# Measurement_REO.net
KiCad netlist of a schematic drawn in Altium Designer
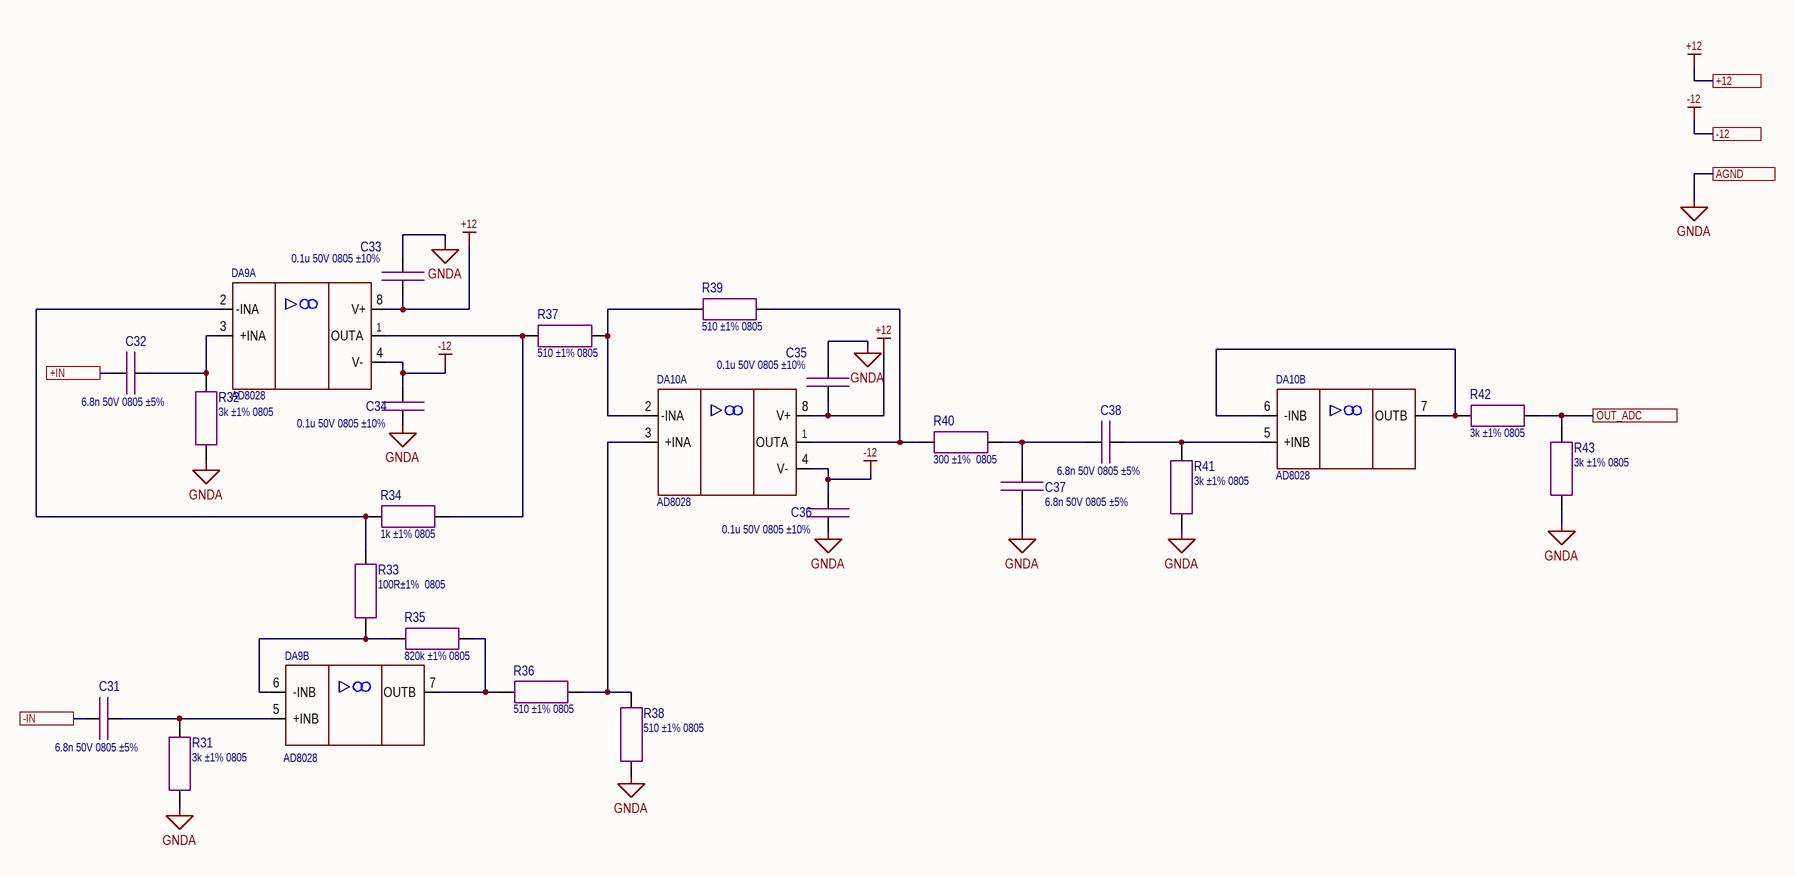
[diagram p0: Measurement_REO.SchDoc]

(export (version "E")
  (design (tool "Eeschema 10.0.6"))
  (components
    (comp (ref "C31")
      (value "6.8n 50V 0805 ±5%")
      (footprint "CAP: SMD 0805 MD IPC 782")
      (libsource (lib "UOMP_capacitors") (part "6.8n 50V 0805 ±5%"))
    )
    (comp (ref "C32")
      (value "6.8n 50V 0805 ±5%")
      (footprint "CAP: SMD 0805 MD IPC 782")
      (libsource (lib "UOMP_capacitors") (part "6.8n 50V 0805 ±5%"))
    )
    (comp (ref "C33")
      (value "0.1u 50V 0805 ±10%")
      (footprint "CAP: SMD 0805 MD IPC 782")
      (libsource (lib "UOMP capacitors") (part "0.1u 50V 0805 ±10%"))
    )
    (comp (ref "C34")
      (value "0.1u 50V 0805 ±10%")
      (footprint "CAP: SMD 0805 MD IPC 782")
      (libsource (lib "UOMP capacitors") (part "0.1u 50V 0805 ±10%"))
    )
    (comp (ref "C35")
      (value "0.1u 50V 0805 ±10%")
      (footprint "CAP: SMD 0805 MD IPC 782")
      (libsource (lib "UOMP capacitors") (part "0.1u 50V 0805 ±10%"))
    )
    (comp (ref "C36")
      (value "0.1u 50V 0805 ±10%")
      (footprint "CAP: SMD 0805 MD IPC 782")
      (libsource (lib "UOMP capacitors") (part "0.1u 50V 0805 ±10%"))
    )
    (comp (ref "C37")
      (value "6.8n 50V 0805 ±5%")
      (footprint "CAP: SMD 0805 MD IPC 782")
      (libsource (lib "UOMP_capacitors") (part "6.8n 50V 0805 ±5%"))
    )
    (comp (ref "C38")
      (value "6.8n 50V 0805 ±5%")
      (footprint "CAP: SMD 0805 MD IPC 782")
      (libsource (lib "UOMP_capacitors") (part "6.8n 50V 0805 ±5%"))
    )
    (comp (ref "DA9")
      (value "AD8028")
      (footprint "IC: SOIC 8")
      (libsource (lib "THE_BOYS_REO") (part "AD8028_part"))
    )
    (comp (ref "DA10")
      (value "AD8028")
      (footprint "IC: SOIC 8")
      (libsource (lib "THE_BOYS_REO") (part "AD8028_part"))
    )
    (comp (ref "R31")
      (value "3k ±1% 0805")
      (footprint "RES: SMD 0805 MD IPC 782")
      (libsource (lib "UOMP_resistors") (part "3k ±1% 0805"))
    )
    (comp (ref "R32")
      (value "3k ±1% 0805")
      (footprint "RES: SMD 0805 MD IPC 782")
      (libsource (lib "UOMP_resistors") (part "3k ±1% 0805"))
    )
    (comp (ref "R33")
      (value "100R±1%  0805")
      (footprint "RES: SMD 0805 MD IPC 782")
      (libsource (lib "UOMP_resistors") (part "100 ±1%  0805"))
    )
    (comp (ref "R34")
      (value "1k ±1% 0805")
      (footprint "RES: SMD 0805 MD IPC 782")
      (libsource (lib "UOMP_resistors") (part "1k ±1% 0805"))
    )
    (comp (ref "R35")
      (value "820k ±1% 0805")
      (footprint "RES: SMD 0805 MD IPC 782")
      (libsource (lib "UOMP_resistors") (part "820k ±1% 0805"))
    )
    (comp (ref "R36")
      (value "510 ±1% 0805")
      (footprint "RES: SMD 0805 MD IPC 782")
      (libsource (lib "UOMP_resistors") (part "510 ±1% 0805"))
    )
    (comp (ref "R37")
      (value "510 ±1% 0805")
      (footprint "RES: SMD 0805 MD IPC 782")
      (libsource (lib "UOMP_resistors") (part "510 ±1% 0805"))
    )
    (comp (ref "R38")
      (value "510 ±1% 0805")
      (footprint "RES: SMD 0805 MD IPC 782")
      (libsource (lib "UOMP_resistors") (part "510 ±1% 0805"))
    )
    (comp (ref "R39")
      (value "510 ±1% 0805")
      (footprint "RES: SMD 0805 MD IPC 782")
      (libsource (lib "UOMP_resistors") (part "510 ±1% 0805"))
    )
    (comp (ref "R40")
      (value "300 ±1%  0805")
      (footprint "RES: SMD 0805 MD IPC 782")
      (libsource (lib "UOMP_resistors") (part "300 ±1%  0805"))
    )
    (comp (ref "R41")
      (value "3k ±1% 0805")
      (footprint "RES: SMD 0805 MD IPC 782")
      (libsource (lib "UOMP_resistors") (part "3k ±1% 0805"))
    )
    (comp (ref "R42")
      (value "3k ±1% 0805")
      (footprint "RES: SMD 0805 MD IPC 782")
      (libsource (lib "UOMP_resistors") (part "3k ±1% 0805"))
    )
    (comp (ref "R43")
      (value "3k ±1% 0805")
      (footprint "RES: SMD 0805 MD IPC 782")
      (libsource (lib "UOMP_resistors") (part "3k ±1% 0805"))
    )
  )
  (nets
    (net (code "1") (name "+12") (class "Default")
      (node (ref "C33") (pin "2") (pinfunction "2_2") (pintype "passive"))
      (node (ref "C35") (pin "2") (pinfunction "2_2") (pintype "passive"))
      (node (ref "DA10") (pin "8") (pinfunction "V+_8") (pintype "passive"))
      (node (ref "DA9") (pin "8") (pinfunction "V+_8") (pintype "passive"))
    )
    (net (code "2") (name "-12") (class "Default")
      (node (ref "C34") (pin "1") (pinfunction "1_1") (pintype "passive"))
      (node (ref "C36") (pin "1") (pinfunction "1_1") (pintype "passive"))
      (node (ref "DA10") (pin "4") (pinfunction "V-_4") (pintype "passive"))
      (node (ref "DA9") (pin "4") (pinfunction "V-_4") (pintype "passive"))
    )
    (net (code "3") (name "/+IN") (class "Default")
      (node (ref "C32") (pin "2") (pinfunction "2_2") (pintype "passive"))
    )
    (net (code "4") (name "/-IN") (class "Default")
      (node (ref "C31") (pin "2") (pinfunction "2_2") (pintype "passive"))
    )
    (net (code "5") (name "/OUT_ADC") (class "Default")
      (node (ref "R42") (pin "2") (pinfunction "2_2") (pintype "passive"))
      (node (ref "R43") (pin "2") (pinfunction "2_2") (pintype "passive"))
    )
    (net (code "6") (name "GNDA") (class "Default")
      (node (ref "C33") (pin "1") (pinfunction "1_1") (pintype "passive"))
      (node (ref "C34") (pin "2") (pinfunction "2_2") (pintype "passive"))
      (node (ref "C35") (pin "1") (pinfunction "1_1") (pintype "passive"))
      (node (ref "C36") (pin "2") (pinfunction "2_2") (pintype "passive"))
      (node (ref "C37") (pin "2") (pinfunction "2_2") (pintype "passive"))
      (node (ref "R31") (pin "2") (pinfunction "2_2") (pintype "passive"))
      (node (ref "R32") (pin "2") (pinfunction "2_2") (pintype "passive"))
      (node (ref "R38") (pin "1") (pinfunction "1_1") (pintype "passive"))
      (node (ref "R41") (pin "2") (pinfunction "2_2") (pintype "passive"))
      (node (ref "R43") (pin "1") (pinfunction "1_1") (pintype "passive"))
    )
    (net (code "7") (name "Net-(C37-Pad1)") (class "Default")
      (node (ref "C37") (pin "1") (pinfunction "1_1") (pintype "passive"))
      (node (ref "C38") (pin "2") (pinfunction "2_2") (pintype "passive"))
      (node (ref "R40") (pin "2") (pinfunction "2_2") (pintype "passive"))
    )
    (net (code "8") (name "Net-(DA9A-+INA)") (class "Default")
      (node (ref "C32") (pin "1") (pinfunction "1_1") (pintype "passive"))
      (node (ref "DA9") (pin "3") (pinfunction "+INA_3") (pintype "passive"))
      (node (ref "R32") (pin "1") (pinfunction "1_1") (pintype "passive"))
    )
    (net (code "9") (name "Net-(DA9A--INA)") (class "Default")
      (node (ref "DA9") (pin "2") (pinfunction "-INA_2") (pintype "passive"))
      (node (ref "R33") (pin "2") (pinfunction "2_2") (pintype "passive"))
      (node (ref "R34") (pin "2") (pinfunction "2_2") (pintype "passive"))
    )
    (net (code "10") (name "Net-(DA9A-OUTA)") (class "Default")
      (node (ref "DA9") (pin "1") (pinfunction "OUTA_1") (pintype "passive"))
      (node (ref "R34") (pin "1") (pinfunction "1_1") (pintype "passive"))
      (node (ref "R37") (pin "1") (pinfunction "1_1") (pintype "passive"))
    )
    (net (code "11") (name "Net-(DA9B-+INB)") (class "Default")
      (node (ref "C31") (pin "1") (pinfunction "1_1") (pintype "passive"))
      (node (ref "DA9") (pin "5") (pinfunction "+INB_5") (pintype "passive"))
      (node (ref "R31") (pin "1") (pinfunction "1_1") (pintype "passive"))
    )
    (net (code "12") (name "Net-(DA9B--INB)") (class "Default")
      (node (ref "DA9") (pin "6") (pinfunction "-INB_6") (pintype "passive"))
      (node (ref "R33") (pin "1") (pinfunction "1_1") (pintype "passive"))
      (node (ref "R35") (pin "2") (pinfunction "2_2") (pintype "passive"))
    )
    (net (code "13") (name "Net-(DA9B-OUTB)") (class "Default")
      (node (ref "DA9") (pin "7") (pinfunction "OUTB_7") (pintype "passive"))
      (node (ref "R35") (pin "1") (pinfunction "1_1") (pintype "passive"))
      (node (ref "R36") (pin "1") (pinfunction "1_1") (pintype "passive"))
    )
    (net (code "14") (name "Net-(DA10A-+INA)") (class "Default")
      (node (ref "DA10") (pin "3") (pinfunction "+INA_3") (pintype "passive"))
      (node (ref "R36") (pin "2") (pinfunction "2_2") (pintype "passive"))
      (node (ref "R38") (pin "2") (pinfunction "2_2") (pintype "passive"))
    )
    (net (code "15") (name "Net-(DA10A--INA)") (class "Default")
      (node (ref "DA10") (pin "2") (pinfunction "-INA_2") (pintype "passive"))
      (node (ref "R37") (pin "2") (pinfunction "2_2") (pintype "passive"))
      (node (ref "R39") (pin "1") (pinfunction "1_1") (pintype "passive"))
    )
    (net (code "16") (name "Net-(DA10A-OUTA)") (class "Default")
      (node (ref "DA10") (pin "1") (pinfunction "OUTA_1") (pintype "passive"))
      (node (ref "R39") (pin "2") (pinfunction "2_2") (pintype "passive"))
      (node (ref "R40") (pin "1") (pinfunction "1_1") (pintype "passive"))
    )
    (net (code "17") (name "Net-(DA10B-+INB)") (class "Default")
      (node (ref "C38") (pin "1") (pinfunction "1_1") (pintype "passive"))
      (node (ref "DA10") (pin "5") (pinfunction "+INB_5") (pintype "passive"))
      (node (ref "R41") (pin "1") (pinfunction "1_1") (pintype "passive"))
    )
    (net (code "18") (name "Net-(DA10B--INB)") (class "Default")
      (node (ref "DA10") (pin "6") (pinfunction "-INB_6") (pintype "passive"))
      (node (ref "DA10") (pin "7") (pinfunction "OUTB_7") (pintype "passive"))
      (node (ref "R42") (pin "1") (pinfunction "1_1") (pintype "passive"))
    )
  )
)
